# frontend.net
KiCad netlist of a schematic drawn in Altium Designer
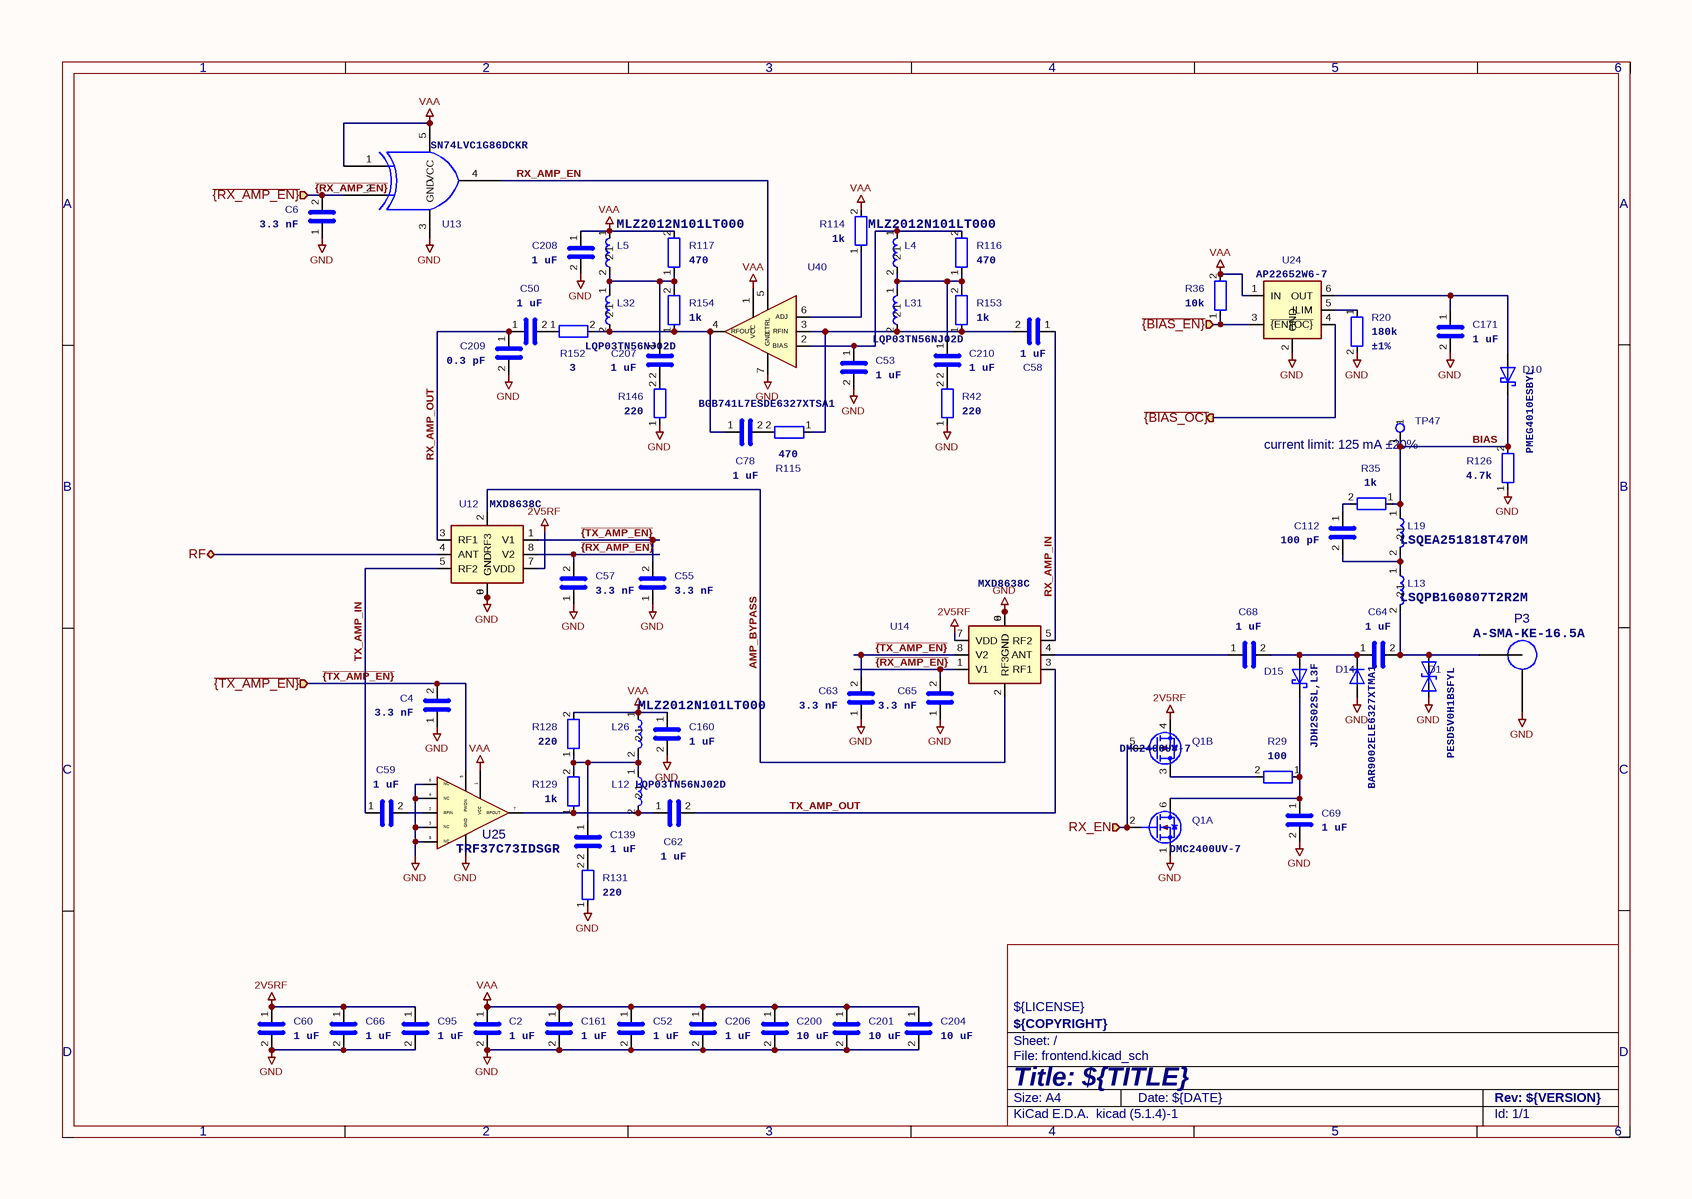
[diagram p0: frontend.SchDoc]

(export (version "E")
  (design (tool "Eeschema 10.0.6"))
  (components
    (comp (ref "C2")
      (value "1 uF")
      (footprint "C_0201_0603Metric")
      (fields (field (name "MANUFACTURER") "Murata") (field (name "PART NUMBER") "GRM033R61A105ME44D"))
      (libsource (lib "Device") (part "C"))
    )
    (comp (ref "C4")
      (value "3.3 nF")
      (footprint "C_0201_0603Metric")
      (fields (field (name "MANUFACTURER") "Murata") (field (name "PART NUMBER") "GRM033R71A332KA01D"))
      (libsource (lib "Device") (part "C"))
    )
    (comp (ref "C6")
      (value "3.3 nF")
      (footprint "C_0201_0603Metric")
      (fields (field (name "MANUFACTURER") "Murata") (field (name "PART NUMBER") "GRM033R71A332KA01D"))
      (libsource (lib "Device") (part "C"))
    )
    (comp (ref "C50")
      (value "1 uF")
      (footprint "C_0201_0603Metric")
      (fields (field (name "MANUFACTURER") "Murata") (field (name "PART NUMBER") "GRM033R61A105ME44D"))
      (libsource (lib "Device") (part "C"))
    )
    (comp (ref "C52")
      (value "1 uF")
      (footprint "C_0201_0603Metric")
      (fields (field (name "MANUFACTURER") "Murata") (field (name "PART NUMBER") "GRM033R61A105ME44D"))
      (libsource (lib "Device") (part "C"))
    )
    (comp (ref "C53")
      (value "1 uF")
      (footprint "C_0201_0603Metric")
      (fields (field (name "MANUFACTURER") "Murata") (field (name "PART NUMBER") "GRM033R61A105ME44D"))
      (libsource (lib "Device") (part "C"))
    )
    (comp (ref "C55")
      (value "3.3 nF")
      (footprint "C_0201_0603Metric")
      (fields (field (name "MANUFACTURER") "Murata") (field (name "PART NUMBER") "GRM033R71A332KA01D"))
      (libsource (lib "Device") (part "C"))
    )
    (comp (ref "C57")
      (value "3.3 nF")
      (footprint "C_0201_0603Metric")
      (fields (field (name "MANUFACTURER") "Murata") (field (name "PART NUMBER") "GRM033R71A332KA01D"))
      (libsource (lib "Device") (part "C"))
    )
    (comp (ref "C58")
      (value "1 uF")
      (footprint "C_0201_0603Metric")
      (fields (field (name "MANUFACTURER") "Murata") (field (name "PART NUMBER") "GRM033R61A105ME44D"))
      (libsource (lib "Device") (part "C"))
    )
    (comp (ref "C59")
      (value "1 uF")
      (footprint "C_0201_0603Metric")
      (fields (field (name "MANUFACTURER") "Murata") (field (name "PART NUMBER") "GRM033R61A105ME44D"))
      (libsource (lib "Device") (part "C"))
    )
    (comp (ref "C60")
      (value "1 uF")
      (footprint "C_0201_0603Metric")
      (fields (field (name "MANUFACTURER") "Murata") (field (name "PART NUMBER") "GRM033R61A105ME44D"))
      (libsource (lib "Device") (part "C"))
    )
    (comp (ref "C62")
      (value "1 uF")
      (footprint "C_0201_0603Metric")
      (fields (field (name "MANUFACTURER") "Murata") (field (name "PART NUMBER") "GRM033R61A105ME44D"))
      (libsource (lib "Device") (part "C"))
    )
    (comp (ref "C63")
      (value "3.3 nF")
      (footprint "C_0201_0603Metric")
      (fields (field (name "MANUFACTURER") "Murata") (field (name "PART NUMBER") "GRM033R71A332KA01D"))
      (libsource (lib "Device") (part "C"))
    )
    (comp (ref "C64")
      (value "1 uF")
      (footprint "C_0402_1005Metric")
      (fields (field (name "MANUFACTURER") "Samsung") (field (name "PART NUMBER") "CL05A105KA5NQNC"))
      (libsource (lib "Device") (part "C"))
    )
    (comp (ref "C65")
      (value "3.3 nF")
      (footprint "C_0201_0603Metric")
      (fields (field (name "MANUFACTURER") "Murata") (field (name "PART NUMBER") "GRM033R71A332KA01D"))
      (libsource (lib "Device") (part "C"))
    )
    (comp (ref "C66")
      (value "1 uF")
      (footprint "C_0201_0603Metric")
      (fields (field (name "MANUFACTURER") "Murata") (field (name "PART NUMBER") "GRM033R61A105ME44D"))
      (libsource (lib "Device") (part "C"))
    )
    (comp (ref "C68")
      (value "1 uF")
      (footprint "C_0201_0603Metric")
      (fields (field (name "MANUFACTURER") "Murata") (field (name "PART NUMBER") "GRM033R61A105ME44D"))
      (libsource (lib "Device") (part "C"))
    )
    (comp (ref "C69")
      (value "1 uF")
      (footprint "C_0201_0603Metric")
      (fields (field (name "MANUFACTURER") "Murata") (field (name "PART NUMBER") "GRM033R61A105ME44D"))
      (libsource (lib "Device") (part "C"))
    )
    (comp (ref "C78")
      (value "1 uF")
      (footprint "C_0201_0603Metric")
      (fields (field (name "MANUFACTURER") "Murata") (field (name "PART NUMBER") "GRM033R61A105ME44D"))
      (libsource (lib "Device") (part "C"))
    )
    (comp (ref "C95")
      (value "1 uF")
      (footprint "C_0201_0603Metric")
      (fields (field (name "MANUFACTURER") "Murata") (field (name "PART NUMBER") "GRM033R61A105ME44D"))
      (libsource (lib "Device") (part "C"))
    )
    (comp (ref "C112")
      (value "100 pF")
      (footprint "C_0201_0603Metric")
      (fields (field (name "MANUFACTURER") "Murata") (field (name "PART NUMBER") "GRM0335C1E101JA01D"))
      (libsource (lib "Device") (part "C"))
    )
    (comp (ref "C139")
      (value "1 uF")
      (footprint "C_0201_0603Metric")
      (fields (field (name "MANUFACTURER") "Murata") (field (name "PART NUMBER") "GRM033R61A105ME44D"))
      (libsource (lib "Device") (part "C"))
    )
    (comp (ref "C160")
      (value "1 uF")
      (footprint "C_0201_0603Metric")
      (fields (field (name "MANUFACTURER") "Murata") (field (name "PART NUMBER") "GRM033R61A105ME44D"))
      (libsource (lib "Device") (part "C"))
    )
    (comp (ref "C161")
      (value "1 uF")
      (footprint "C_0201_0603Metric")
      (fields (field (name "MANUFACTURER") "Murata") (field (name "PART NUMBER") "GRM033R61A105ME44D"))
      (libsource (lib "Device") (part "C"))
    )
    (comp (ref "C171")
      (value "1 uF")
      (footprint "C_0402_1005Metric")
      (fields (field (name "MANUFACTURER") "Samsung") (field (name "PART NUMBER") "CL05A105KA5NQNC"))
      (libsource (lib "Device") (part "C"))
    )
    (comp (ref "C200")
      (value "10 uF")
      (footprint "C_0805_2012Metric")
      (fields (field (name "MANUFACTURER") "Samsung") (field (name "PART NUMBER") "CL21A106KOQNNNE"))
      (libsource (lib "Device") (part "C"))
    )
    (comp (ref "C201")
      (value "10 uF")
      (footprint "C_0805_2012Metric")
      (fields (field (name "MANUFACTURER") "Samsung") (field (name "PART NUMBER") "CL21A106KOQNNNE"))
      (libsource (lib "Device") (part "C"))
    )
    (comp (ref "C204")
      (value "10 uF")
      (footprint "C_0805_2012Metric")
      (fields (field (name "MANUFACTURER") "Samsung") (field (name "PART NUMBER") "CL21A106KOQNNNE"))
      (libsource (lib "Device") (part "C"))
    )
    (comp (ref "C206")
      (value "1 uF")
      (footprint "C_0201_0603Metric")
      (fields (field (name "MANUFACTURER") "Murata") (field (name "PART NUMBER") "GRM033R61A105ME44D"))
      (libsource (lib "Device") (part "C"))
    )
    (comp (ref "C207")
      (value "1 uF")
      (footprint "C_0201_0603Metric")
      (fields (field (name "MANUFACTURER") "Murata") (field (name "PART NUMBER") "GRM033R61A105ME44D"))
      (libsource (lib "Device") (part "C"))
    )
    (comp (ref "C208")
      (value "1 uF")
      (footprint "C_0201_0603Metric")
      (fields (field (name "MANUFACTURER") "Murata") (field (name "PART NUMBER") "GRM033R61A105ME44D"))
      (libsource (lib "Device") (part "C"))
    )
    (comp (ref "C209")
      (value "0.3 pF")
      (footprint "C_0201_0603Metric")
      (fields (field (name "MANUFACTURER") "Murata") (field (name "PART NUMBER") "GRM0335C1ER30BA01D"))
      (libsource (lib "Device") (part "C"))
    )
    (comp (ref "C210")
      (value "1 uF")
      (footprint "C_0201_0603Metric")
      (fields (field (name "MANUFACTURER") "Murata") (field (name "PART NUMBER") "GRM033R61A105ME44D"))
      (libsource (lib "Device") (part "C"))
    )
    (comp (ref "D1")
      (value "TVS")
      (footprint "TSSLP-2-1")
      (fields (field (name "MANUFACTURER") "Nexperia") (field (name "PART NUMBER") "PESD5V0H1BSFYL"))
      (libsource (lib "Device") (part "D_TVS"))
    )
    (comp (ref "D10")
      (value "Schottky")
      (footprint "TSLP-2-19")
      (fields (field (name "MANUFACTURER") "Nexperia") (field (name "PART NUMBER") "PMEG4010ESBYL"))
      (libsource (lib "Device") (part "D_Schottky"))
    )
    (comp (ref "D14")
      (value "PIN")
      (footprint "TSLP-2-19")
      (fields (field (name "MANUFACTURER") "Infineon") (field (name "PART NUMBER") "BAR9002ELE6327XTMA1"))
      (libsource (lib "Device") (part "D"))
    )
    (comp (ref "D15")
      (value "Schottky")
      (footprint "TSSLP-2-1")
      (fields (field (name "MANUFACTURER") "Toshiba") (field (name "PART NUMBER") "JDH2S02SL,L3F"))
      (libsource (lib "Device") (part "D_Schottky"))
    )
    (comp (ref "L4")
      (value "100 uH")
      (footprint "L_TDK_MLZ2012_h1.25mm")
      (fields (field (name "MANUFACTURER") "TDK") (field (name "PART NUMBER") "MLZ2012N101LT000"))
      (libsource (lib "Device") (part "L"))
    )
    (comp (ref "L5")
      (value "100 uH")
      (footprint "L_TDK_MLZ2012_h1.25mm")
      (fields (field (name "MANUFACTURER") "TDK") (field (name "PART NUMBER") "MLZ2012N101LT000"))
      (libsource (lib "Device") (part "L"))
    )
    (comp (ref "L12")
      (value "56 nH")
      (footprint "L_0201_0603Metric")
      (fields (field (name "MANUFACTURER") "Murata") (field (name "PART NUMBER") "LQP03TN56NJ02D"))
      (libsource (lib "") (part "L_1"))
    )
    (comp (ref "L13")
      (value "2.2 uH")
      (footprint "L_0603_1608Metric")
      (fields (field (name "MANUFACTURER") "Taiyo Yuden") (field (name "PART NUMBER") "LSQPB160807T2R2M"))
      (libsource (lib "") (part "L_1"))
    )
    (comp (ref "L19")
      (value "47 uH")
      (footprint "L_Taiyo-Yuden_A251818")
      (fields (field (name "MANUFACTURER") "Taiyo Yuden") (field (name "PART NUMBER") "LSQEA251818T470M"))
      (libsource (lib "") (part "L_1"))
    )
    (comp (ref "L26")
      (value "100 uH")
      (footprint "L_TDK_MLZ2012_h1.25mm")
      (fields (field (name "MANUFACTURER") "TDK") (field (name "PART NUMBER") "MLZ2012N101LT000"))
      (libsource (lib "") (part "L_1"))
    )
    (comp (ref "L31")
      (value "56 nH")
      (footprint "L_0201_0603Metric")
      (fields (field (name "MANUFACTURER") "Murata") (field (name "PART NUMBER") "LQP03TN56NJ02D"))
      (libsource (lib "Device") (part "L"))
    )
    (comp (ref "L32")
      (value "56 nH")
      (footprint "L_0201_0603Metric")
      (fields (field (name "MANUFACTURER") "Murata") (field (name "PART NUMBER") "LQP03TN56NJ02D"))
      (libsource (lib "Device") (part "L"))
    )
    (comp (ref "P3")
      (value "SMA")
      (footprint "SMA_MyAntenna_A-SMA-KE-16.5A_EdgeMount")
      (fields (field (name "MANUFACTURER") "MyAntenna") (field (name "PART NUMBER") "A-SMA-KE-16.5A"))
      (libsource (lib "hackrf") (part "GSG-RF-CONN"))
    )
    (comp (ref "Q1")
      (value "NMOS/PMOS")
      (footprint "SOT-563")
      (fields (field (name "MANUFACTURER") "Diodes Inc.") (field (name "PART NUMBER") "DMC2400UV-7"))
      (libsource (lib "praline") (part "Q_Dual_NMOS_PMOS_S1G1D2S2G2D1"))
    )
    (comp (ref "R20")
      (value "180k")
      (footprint "R_0402_1005Metric")
      (fields
        (field (name "MANUFACTURER") "Yageo")
        (field (name "PART NUMBER") "RC0402FR-07180KL")
        (field (name "TOLERANCE") "±1%")
      )
      (libsource (lib "") (part "R_3"))
    )
    (comp (ref "R29")
      (value "100")
      (footprint "R_0201_0603Metric")
      (fields (field (name "MANUFACTURER") "Yageo") (field (name "PART NUMBER") "RC0201JR-07100RL"))
      (libsource (lib "") (part "R_1"))
    )
    (comp (ref "R35")
      (value "1k")
      (footprint "R_0201_0603Metric")
      (fields (field (name "MANUFACTURER") "Yageo") (field (name "PART NUMBER") "RC0201FR-071KL"))
      (libsource (lib "") (part "R_3"))
    )
    (comp (ref "R36")
      (value "10k")
      (footprint "R_0402_1005Metric")
      (fields (field (name "MANUFACTURER") "Yageo") (field (name "PART NUMBER") "RC0402JR-0710KL"))
      (libsource (lib "Device") (part "R"))
    )
    (comp (ref "R42")
      (value "220")
      (footprint "R_0201_0603Metric")
      (fields (field (name "MANUFACTURER") "Yageo") (field (name "PART NUMBER") "RC0201JR-07220RL"))
      (libsource (lib "Device") (part "R"))
    )
    (comp (ref "R114")
      (value "1k")
      (footprint "R_0201_0603Metric")
      (fields (field (name "MANUFACTURER") "Yageo") (field (name "PART NUMBER") "RC0201FR-071KL"))
      (libsource (lib "") (part "R_2"))
    )
    (comp (ref "R115")
      (value "470")
      (footprint "R_0201_0603Metric")
      (fields (field (name "MANUFACTURER") "Yageo") (field (name "PART NUMBER") "RC0201JR-07470RL"))
      (libsource (lib "") (part "R_1"))
    )
    (comp (ref "R116")
      (value "470")
      (footprint "R_0201_0603Metric")
      (fields (field (name "MANUFACTURER") "Yageo") (field (name "PART NUMBER") "RC0201JR-07470RL"))
      (libsource (lib "Device") (part "R"))
    )
    (comp (ref "R117")
      (value "470")
      (footprint "R_0201_0603Metric")
      (fields (field (name "MANUFACTURER") "Yageo") (field (name "PART NUMBER") "RC0201JR-07470RL"))
      (libsource (lib "Device") (part "R"))
    )
    (comp (ref "R126")
      (value "4.7k")
      (footprint "R_0201_0603Metric")
      (fields (field (name "MANUFACTURER") "Yageo") (field (name "PART NUMBER") "RC0201FR-074K7L"))
      (libsource (lib "Device") (part "R"))
    )
    (comp (ref "R128")
      (value "220")
      (footprint "R_0201_0603Metric")
      (fields (field (name "MANUFACTURER") "Yageo") (field (name "PART NUMBER") "RC0201JR-07220RL"))
      (libsource (lib "") (part "R_2"))
    )
    (comp (ref "R129")
      (value "1k")
      (footprint "R_0201_0603Metric")
      (fields (field (name "MANUFACTURER") "Yageo") (field (name "PART NUMBER") "RC0201FR-071KL"))
      (libsource (lib "") (part "R_2"))
    )
    (comp (ref "R131")
      (value "220")
      (footprint "R_0201_0603Metric")
      (fields (field (name "MANUFACTURER") "Yageo") (field (name "PART NUMBER") "RC0201JR-07220RL"))
      (libsource (lib "Device") (part "R"))
    )
    (comp (ref "R146")
      (value "220")
      (footprint "R_0201_0603Metric")
      (fields (field (name "MANUFACTURER") "Yageo") (field (name "PART NUMBER") "RC0201JR-07220RL"))
      (libsource (lib "") (part "R_2"))
    )
    (comp (ref "R152")
      (value "3")
      (footprint "R_0201_0603Metric")
      (fields (field (name "MANUFACTURER") "Yageo") (field (name "PART NUMBER") "RC0201JR-073RL"))
      (libsource (lib "Device") (part "R"))
    )
    (comp (ref "R153")
      (value "1k")
      (footprint "R_0201_0603Metric")
      (fields (field (name "MANUFACTURER") "Yageo") (field (name "PART NUMBER") "RC0201FR-071KL"))
      (libsource (lib "Device") (part "R"))
    )
    (comp (ref "R154")
      (value "1k")
      (footprint "R_0201_0603Metric")
      (fields (field (name "MANUFACTURER") "Yageo") (field (name "PART NUMBER") "RC0201FR-071KL"))
      (libsource (lib "Device") (part "R"))
    )
    (comp (ref "TP47")
      (value "TestPoint")
      (footprint "TestPoint_Pad_D1.0mm")
      (libsource (lib "Connector") (part "TestPoint"))
    )
    (comp (ref "U12")
      (value "MXD8638C")
      (footprint "MXD8638C")
      (fields (field (name "MANUFACTURER") "Maxscend") (field (name "PART NUMBER") "MXD8638C"))
      (libsource (lib "") (part "MXD8638_1"))
    )
    (comp (ref "U13")
      (value "74LVC1G86")
      (footprint "SOT-353_SC-70-5")
      (fields (field (name "MANUFACTURER") "UMW") (field (name "PART NUMBER") "SN74LVC1G86DCKR"))
      (libsource (lib "74xGxx") (part "74LVC1G86"))
    )
    (comp (ref "U14")
      (value "MXD8638C")
      (footprint "MXD8638C")
      (fields (field (name "MANUFACTURER") "Maxscend") (field (name "PART NUMBER") "MXD8638C"))
      (libsource (lib "praline") (part "MXD8638"))
    )
    (comp (ref "U24")
      (value "AP22652")
      (footprint "TSOP-6_1.65x3.05mm_P0.95mm")
      (fields (field (name "MANUFACTURER") "Diodes Inc.") (field (name "PART NUMBER") "AP22652W6-7"))
      (libsource (lib "Power_Management") (part "BD2243G"))
    )
    (comp (ref "U25")
      (value "TRF37C73")
      (footprint "WSON-8-1EP_2x2mm_P0.5mm_EP0.9x1.6mm")
      (fields (field (name "MANUFACTURER") "Texas Instruments") (field (name "PART NUMBER") "TRF37C73IDSGR"))
      (libsource (lib "praline") (part "TRF37A73"))
    )
    (comp (ref "U40")
      (value "BGB741L7ESD")
      (footprint "TSLP-7-1")
      (fields (field (name "MANUFACTURER") "Infineon") (field (name "PART NUMBER") "BGB741L7ESDE6327XTSA1"))
      (libsource (lib "praline") (part "BGB741L7ESD"))
    )
  )
  (nets
    (net (code "1") (name "/AMP_BYPASS") (class "Default")
      (node (ref "U12") (pin "2") (pinfunction "RF3_2") (pintype "passive"))
      (node (ref "U14") (pin "2") (pinfunction "RF3_2") (pintype "passive"))
    )
    (net (code "2") (name "/BIAS") (class "Default")
      (node (ref "D10") (pin "1") (pinfunction "K_1") (pintype "passive"))
      (node (ref "L19") (pin "1") (pinfunction "1_1") (pintype "passive"))
      (node (ref "R126") (pin "2") (pinfunction "2_2") (pintype "passive"))
      (node (ref "R35") (pin "1") (pinfunction "1_1") (pintype "passive"))
      (node (ref "TP47") (pin "1") (pinfunction "1_1") (pintype "passive"))
    )
    (net (code "3") (name "/RF") (class "Default")
      (node (ref "U12") (pin "4") (pinfunction "ANT_4") (pintype "passive"))
    )
    (net (code "4") (name "/RX_AMP_EN") (class "Default")
      (node (ref "U13") (pin "4") (pinfunction "4_4") (pintype "passive"))
      (node (ref "U40") (pin "5") (pinfunction "CTRL_5") (pintype "passive"))
    )
    (net (code "5") (name "/RX_AMP_IN") (class "Default")
      (node (ref "C58") (pin "1") (pinfunction "1_1") (pintype "passive"))
      (node (ref "U14") (pin "5") (pinfunction "RF2_5") (pintype "passive"))
    )
    (net (code "6") (name "/RX_AMP_OUT") (class "Default")
      (node (ref "C209") (pin "1") (pinfunction "1_1") (pintype "passive"))
      (node (ref "C50") (pin "1") (pinfunction "1_1") (pintype "passive"))
      (node (ref "U12") (pin "3") (pinfunction "RF1_3") (pintype "passive"))
    )
    (net (code "7") (name "/RX_EN") (class "Default")
      (node (ref "Q1") (pin "2") (pinfunction "G_2") (pintype "passive"))
      (node (ref "Q1") (pin "5") (pinfunction "G_5") (pintype "passive"))
    )
    (net (code "8") (name "/TX_AMP_IN") (class "Default")
      (node (ref "C59") (pin "1") (pinfunction "1_1") (pintype "passive"))
      (node (ref "U12") (pin "5") (pinfunction "RF2_5") (pintype "passive"))
    )
    (net (code "9") (name "/TX_AMP_OUT") (class "Default")
      (node (ref "C62") (pin "2") (pinfunction "2_2") (pintype "passive"))
      (node (ref "U14") (pin "3") (pinfunction "RF1_3") (pintype "passive"))
    )
    (net (code "10") (name "/~{{BIAS_EN}}") (class "Default")
      (node (ref "R36") (pin "1") (pinfunction "1_1") (pintype "passive"))
      (node (ref "U24") (pin "3") (pinfunction "~{{EN}}_3") (pintype "passive"))
    )
    (net (code "11") (name "/~{{BIAS_OC}}") (class "Default")
      (node (ref "U24") (pin "4") (pinfunction "~{{OC}}_4") (pintype "passive"))
    )
    (net (code "12") (name "/~{{RX_AMP_EN}}") (class "Default")
      (node (ref "C57") (pin "2") (pinfunction "2_2") (pintype "passive"))
      (node (ref "C6") (pin "2") (pinfunction "2_2") (pintype "passive"))
      (node (ref "C65") (pin "2") (pinfunction "2_2") (pintype "passive"))
      (node (ref "U12") (pin "8") (pinfunction "V2_8") (pintype "passive"))
      (node (ref "U13") (pin "2") (pinfunction "2_2") (pintype "passive"))
      (node (ref "U14") (pin "1") (pinfunction "V1_1") (pintype "passive"))
    )
    (net (code "13") (name "/~{{TX_AMP_EN}}") (class "Default")
      (node (ref "C4") (pin "2") (pinfunction "2_2") (pintype "passive"))
      (node (ref "C55") (pin "2") (pinfunction "2_2") (pintype "passive"))
      (node (ref "C63") (pin "2") (pinfunction "2_2") (pintype "passive"))
      (node (ref "U12") (pin "1") (pinfunction "V1_1") (pintype "passive"))
      (node (ref "U14") (pin "8") (pinfunction "V2_8") (pintype "passive"))
      (node (ref "U25") (pin "5") (pinfunction "PWDN_5") (pintype "passive"))
    )
    (net (code "14") (name "2V5RF") (class "Default")
      (node (ref "C60") (pin "1") (pinfunction "1_1") (pintype "passive"))
      (node (ref "C66") (pin "1") (pinfunction "1_1") (pintype "passive"))
      (node (ref "C95") (pin "1") (pinfunction "1_1") (pintype "passive"))
      (node (ref "Q1") (pin "4") (pinfunction "S_4") (pintype "passive"))
      (node (ref "U12") (pin "7") (pinfunction "VDD_7") (pintype "passive"))
      (node (ref "U14") (pin "7") (pinfunction "VDD_7") (pintype "passive"))
    )
    (net (code "15") (name "GND") (class "Default")
      (node (ref "C160") (pin "2") (pinfunction "2_2") (pintype "passive"))
      (node (ref "C161") (pin "2") (pinfunction "2_2") (pintype "passive"))
      (node (ref "C171") (pin "2") (pinfunction "2_2") (pintype "passive"))
      (node (ref "C2") (pin "2") (pinfunction "2_2") (pintype "passive"))
      (node (ref "C200") (pin "2") (pinfunction "2_2") (pintype "passive"))
      (node (ref "C201") (pin "2") (pinfunction "2_2") (pintype "passive"))
      (node (ref "C204") (pin "2") (pinfunction "2_2") (pintype "passive"))
      (node (ref "C206") (pin "2") (pinfunction "2_2") (pintype "passive"))
      (node (ref "C208") (pin "2") (pinfunction "2_2") (pintype "passive"))
      (node (ref "C209") (pin "2") (pinfunction "2_2") (pintype "passive"))
      (node (ref "C4") (pin "1") (pinfunction "1_1") (pintype "passive"))
      (node (ref "C52") (pin "2") (pinfunction "2_2") (pintype "passive"))
      (node (ref "C53") (pin "2") (pinfunction "2_2") (pintype "passive"))
      (node (ref "C55") (pin "1") (pinfunction "1_1") (pintype "passive"))
      (node (ref "C57") (pin "1") (pinfunction "1_1") (pintype "passive"))
      (node (ref "C6") (pin "1") (pinfunction "1_1") (pintype "passive"))
      (node (ref "C60") (pin "2") (pinfunction "2_2") (pintype "passive"))
      (node (ref "C63") (pin "1") (pinfunction "1_1") (pintype "passive"))
      (node (ref "C65") (pin "1") (pinfunction "1_1") (pintype "passive"))
      (node (ref "C66") (pin "2") (pinfunction "2_2") (pintype "passive"))
      (node (ref "C69") (pin "2") (pinfunction "2_2") (pintype "passive"))
      (node (ref "C95") (pin "2") (pinfunction "2_2") (pintype "passive"))
      (node (ref "D1") (pin "2") (pinfunction "A2_2") (pintype "passive"))
      (node (ref "D14") (pin "2") (pinfunction "A_2") (pintype "passive"))
      (node (ref "P3") (pin "2") (pinfunction "GND_2") (pintype "passive"))
      (node (ref "Q1") (pin "1") (pinfunction "S_1") (pintype "passive"))
      (node (ref "R126") (pin "1") (pinfunction "1_1") (pintype "passive"))
      (node (ref "R131") (pin "1") (pinfunction "1_1") (pintype "passive"))
      (node (ref "R146") (pin "1") (pinfunction "1_1") (pintype "passive"))
      (node (ref "R20") (pin "2") (pinfunction "2_2") (pintype "passive"))
      (node (ref "R42") (pin "1") (pinfunction "1_1") (pintype "passive"))
      (node (ref "U12") (pin "6") (pinfunction "GND_6") (pintype "passive"))
      (node (ref "U12") (pin "9") (pinfunction "GND_9") (pintype "passive"))
      (node (ref "U13") (pin "3") (pinfunction "GND_3") (pintype "passive"))
      (node (ref "U14") (pin "6") (pinfunction "GND_6") (pintype "passive"))
      (node (ref "U14") (pin "9") (pinfunction "GND_9") (pintype "passive"))
      (node (ref "U24") (pin "2") (pinfunction "GND_2") (pintype "passive"))
      (node (ref "U25") (pin "3") (pinfunction "NC_3") (pintype "passive"))
      (node (ref "U25") (pin "4") (pinfunction "NC_4") (pintype "passive"))
      (node (ref "U25") (pin "6") (pinfunction "NC_6") (pintype "passive"))
      (node (ref "U25") (pin "8") (pinfunction "NC_8") (pintype "passive"))
      (node (ref "U25") (pin "9") (pinfunction "GND_9") (pintype "passive"))
      (node (ref "U40") (pin "7") (pinfunction "GND_7") (pintype "passive"))
    )
    (net (code "16") (name "Net-(C50-Pad2)") (class "Default")
      (node (ref "C50") (pin "2") (pinfunction "2_2") (pintype "passive"))
      (node (ref "R152") (pin "1") (pinfunction "1_1") (pintype "passive"))
    )
    (net (code "17") (name "Net-(C78-Pad2)") (class "Default")
      (node (ref "C78") (pin "2") (pinfunction "2_2") (pintype "passive"))
      (node (ref "R115") (pin "2") (pinfunction "2_2") (pintype "passive"))
    )
    (net (code "18") (name "Net-(C112-Pad1)") (class "Default")
      (node (ref "C112") (pin "1") (pinfunction "1_1") (pintype "passive"))
      (node (ref "R35") (pin "2") (pinfunction "2_2") (pintype "passive"))
    )
    (net (code "19") (name "Net-(C112-Pad2)") (class "Default")
      (node (ref "C112") (pin "2") (pinfunction "2_2") (pintype "passive"))
      (node (ref "L13") (pin "1") (pinfunction "1_1") (pintype "passive"))
      (node (ref "L19") (pin "2") (pinfunction "2_2") (pintype "passive"))
    )
    (net (code "20") (name "Net-(C139-Pad1)") (class "Default")
      (node (ref "C139") (pin "1") (pinfunction "1_1") (pintype "passive"))
      (node (ref "L12") (pin "1") (pinfunction "1_1") (pintype "passive"))
      (node (ref "L26") (pin "2") (pinfunction "2_2") (pintype "passive"))
      (node (ref "R128") (pin "1") (pinfunction "1_1") (pintype "passive"))
      (node (ref "R129") (pin "2") (pinfunction "2_2") (pintype "passive"))
    )
    (net (code "21") (name "Net-(C139-Pad2)") (class "Default")
      (node (ref "C139") (pin "2") (pinfunction "2_2") (pintype "passive"))
      (node (ref "R131") (pin "2") (pinfunction "2_2") (pintype "passive"))
    )
    (net (code "22") (name "Net-(C207-Pad1)") (class "Default")
      (node (ref "C207") (pin "1") (pinfunction "1_1") (pintype "passive"))
      (node (ref "L32") (pin "1") (pinfunction "1_1") (pintype "passive"))
      (node (ref "L5") (pin "2") (pinfunction "2_2") (pintype "passive"))
      (node (ref "R117") (pin "1") (pinfunction "1_1") (pintype "passive"))
      (node (ref "R154") (pin "2") (pinfunction "2_2") (pintype "passive"))
    )
    (net (code "23") (name "Net-(C207-Pad2)") (class "Default")
      (node (ref "C207") (pin "2") (pinfunction "2_2") (pintype "passive"))
      (node (ref "R146") (pin "2") (pinfunction "2_2") (pintype "passive"))
    )
    (net (code "24") (name "Net-(C210-Pad1)") (class "Default")
      (node (ref "C210") (pin "1") (pinfunction "1_1") (pintype "passive"))
      (node (ref "L31") (pin "1") (pinfunction "1_1") (pintype "passive"))
      (node (ref "L4") (pin "2") (pinfunction "2_2") (pintype "passive"))
      (node (ref "R116") (pin "1") (pinfunction "1_1") (pintype "passive"))
      (node (ref "R153") (pin "2") (pinfunction "2_2") (pintype "passive"))
    )
    (net (code "25") (name "Net-(C210-Pad2)") (class "Default")
      (node (ref "C210") (pin "2") (pinfunction "2_2") (pintype "passive"))
      (node (ref "R42") (pin "2") (pinfunction "2_2") (pintype "passive"))
    )
    (net (code "26") (name "Net-(D1-A1)") (class "Default")
      (node (ref "C64") (pin "2") (pinfunction "2_2") (pintype "passive"))
      (node (ref "D1") (pin "1") (pinfunction "A1_1") (pintype "passive"))
      (node (ref "L13") (pin "2") (pinfunction "2_2") (pintype "passive"))
      (node (ref "P3") (pin "1") (pinfunction "RF_1") (pintype "passive"))
    )
    (net (code "27") (name "Net-(D10-A)") (class "Default")
      (node (ref "C171") (pin "1") (pinfunction "1_1") (pintype "passive"))
      (node (ref "D10") (pin "2") (pinfunction "A_2") (pintype "passive"))
      (node (ref "U24") (pin "6") (pinfunction "OUT_6") (pintype "passive"))
    )
    (net (code "28") (name "Net-(D14-K)") (class "Default")
      (node (ref "C64") (pin "1") (pinfunction "1_1") (pintype "passive"))
      (node (ref "C68") (pin "2") (pinfunction "2_2") (pintype "passive"))
      (node (ref "D14") (pin "1") (pinfunction "K_1") (pintype "passive"))
      (node (ref "D15") (pin "2") (pinfunction "A_2") (pintype "passive"))
    )
    (net (code "29") (name "Net-(D15-K)") (class "Default")
      (node (ref "C69") (pin "1") (pinfunction "1_1") (pintype "passive"))
      (node (ref "D15") (pin "1") (pinfunction "K_1") (pintype "passive"))
      (node (ref "Q1") (pin "6") (pinfunction "D_6") (pintype "passive"))
      (node (ref "R29") (pin "1") (pinfunction "1_1") (pintype "passive"))
    )
    (net (code "30") (name "Net-(Q1B-D)") (class "Default")
      (node (ref "Q1") (pin "3") (pinfunction "D_3") (pintype "passive"))
      (node (ref "R29") (pin "2") (pinfunction "2_2") (pintype "passive"))
    )
    (net (code "31") (name "Net-(U14-ANT)") (class "Default")
      (node (ref "C68") (pin "1") (pinfunction "1_1") (pintype "passive"))
      (node (ref "U14") (pin "4") (pinfunction "ANT_4") (pintype "passive"))
    )
    (net (code "32") (name "Net-(U24-ILIM)") (class "Default")
      (node (ref "R20") (pin "1") (pinfunction "1_1") (pintype "passive"))
      (node (ref "U24") (pin "5") (pinfunction "ILIM_5") (pintype "passive"))
    )
    (net (code "33") (name "Net-(U25-RFIN)") (class "Default")
      (node (ref "C59") (pin "2") (pinfunction "2_2") (pintype "passive"))
      (node (ref "U25") (pin "2") (pinfunction "RFIN_2") (pintype "passive"))
    )
    (net (code "34") (name "Net-(U25-RFOUT)") (class "Default")
      (node (ref "C62") (pin "1") (pinfunction "1_1") (pintype "passive"))
      (node (ref "L12") (pin "2") (pinfunction "2_2") (pintype "passive"))
      (node (ref "R129") (pin "1") (pinfunction "1_1") (pintype "passive"))
      (node (ref "U25") (pin "7") (pinfunction "RFOUT_7") (pintype "passive"))
    )
    (net (code "35") (name "Net-(U40-ADJ)") (class "Default")
      (node (ref "R114") (pin "1") (pinfunction "1_1") (pintype "passive"))
      (node (ref "U40") (pin "6") (pinfunction "ADJ_6") (pintype "passive"))
    )
    (net (code "36") (name "Net-(U40-BIAS)") (class "Default")
      (node (ref "C53") (pin "1") (pinfunction "1_1") (pintype "passive"))
      (node (ref "L4") (pin "1") (pinfunction "1_1") (pintype "passive"))
      (node (ref "R116") (pin "2") (pinfunction "2_2") (pintype "passive"))
      (node (ref "U40") (pin "2") (pinfunction "BIAS_2") (pintype "passive"))
    )
    (net (code "37") (name "Net-(U40-RFIN)") (class "Default")
      (node (ref "C58") (pin "2") (pinfunction "2_2") (pintype "passive"))
      (node (ref "L31") (pin "2") (pinfunction "2_2") (pintype "passive"))
      (node (ref "R115") (pin "1") (pinfunction "1_1") (pintype "passive"))
      (node (ref "R153") (pin "1") (pinfunction "1_1") (pintype "passive"))
      (node (ref "U40") (pin "3") (pinfunction "RFIN_3") (pintype "passive"))
    )
    (net (code "38") (name "Net-(U40-RFOUT)") (class "Default")
      (node (ref "C78") (pin "1") (pinfunction "1_1") (pintype "passive"))
      (node (ref "L32") (pin "2") (pinfunction "2_2") (pintype "passive"))
      (node (ref "R152") (pin "2") (pinfunction "2_2") (pintype "passive"))
      (node (ref "R154") (pin "1") (pinfunction "1_1") (pintype "passive"))
      (node (ref "U40") (pin "4") (pinfunction "RFOUT_4") (pintype "passive"))
    )
    (net (code "39") (name "VAA") (class "Default")
      (node (ref "C160") (pin "1") (pinfunction "1_1") (pintype "passive"))
      (node (ref "C161") (pin "1") (pinfunction "1_1") (pintype "passive"))
      (node (ref "C2") (pin "1") (pinfunction "1_1") (pintype "passive"))
      (node (ref "C200") (pin "1") (pinfunction "1_1") (pintype "passive"))
      (node (ref "C201") (pin "1") (pinfunction "1_1") (pintype "passive"))
      (node (ref "C204") (pin "1") (pinfunction "1_1") (pintype "passive"))
      (node (ref "C206") (pin "1") (pinfunction "1_1") (pintype "passive"))
      (node (ref "C208") (pin "1") (pinfunction "1_1") (pintype "passive"))
      (node (ref "C52") (pin "1") (pinfunction "1_1") (pintype "passive"))
      (node (ref "L26") (pin "1") (pinfunction "1_1") (pintype "passive"))
      (node (ref "L5") (pin "1") (pinfunction "1_1") (pintype "passive"))
      (node (ref "R114") (pin "2") (pinfunction "2_2") (pintype "passive"))
      (node (ref "R117") (pin "2") (pinfunction "2_2") (pintype "passive"))
      (node (ref "R128") (pin "2") (pinfunction "2_2") (pintype "passive"))
      (node (ref "R36") (pin "2") (pinfunction "2_2") (pintype "passive"))
      (node (ref "U13") (pin "1") (pinfunction "1_1") (pintype "passive"))
      (node (ref "U13") (pin "5") (pinfunction "VCC_5") (pintype "passive"))
      (node (ref "U24") (pin "1") (pinfunction "IN_1") (pintype "passive"))
      (node (ref "U25") (pin "1") (pinfunction "VCC_1") (pintype "passive"))
      (node (ref "U40") (pin "1") (pinfunction "VCC_1") (pintype "passive"))
    )
  )
)
